# mc34063.net
KiCad netlist of a schematic drawn in EAGLE
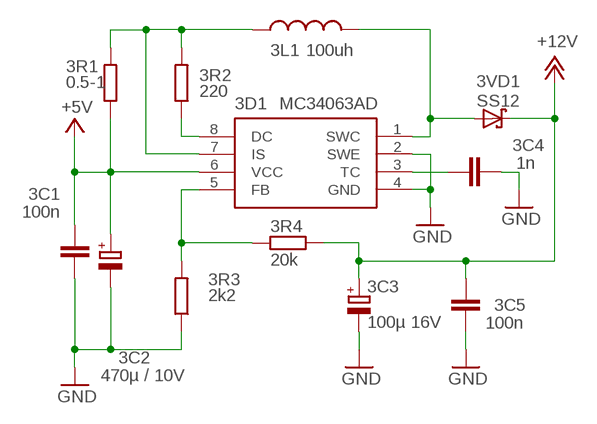
[diagram p0: schematic, sheet 2]

(export (version "E")
  (design (tool "Eeschema 10.0.6"))
  (components
    (comp (ref "3C1")
      (value "100n")
      (footprint "eagle-import:C025-024X044")
      (libsource (lib "eagle-import") (part "C-EU025-024X044"))
    )
    (comp (ref "3C2")
      (value "470µ / 10V")
      (footprint "eagle-import:RCL_E3,5-8")
      (libsource (lib "eagle-import") (part "RCL_CPOL-EUE3.5-8"))
    )
    (comp (ref "3C3")
      (value "100µ 16V")
      (footprint "eagle-import:RCL_E3,5-8")
      (libsource (lib "eagle-import") (part "RCL_CPOL-EUE3.5-8"))
    )
    (comp (ref "3C4")
      (value "1n")
      (footprint "eagle-import:C025-025X050")
      (libsource (lib "eagle-import") (part "rcl_C-EU025-025X050"))
    )
    (comp (ref "3C5")
      (value "100n")
      (footprint "eagle-import:C025-025X050")
      (libsource (lib "eagle-import") (part "rcl_C-EU025-025X050"))
    )
    (comp (ref "3D1")
      (value "MC34063AD")
      (footprint "eagle-import:SOIC8")
      (libsource (lib "eagle-import") (part "MC34063AD"))
    )
    (comp (ref "3L1")
      (value "100uh")
      (footprint "eagle-import:0207_10")
      (libsource (lib "eagle-import") (part "L-US0207/10"))
    )
    (comp (ref "3R1")
      (value "0.5-1")
      (footprint "eagle-import:0204_7")
      (libsource (lib "eagle-import") (part "R-EU_0204/7"))
    )
    (comp (ref "3R2")
      (value "220")
      (footprint "eagle-import:0204_7")
      (libsource (lib "eagle-import") (part "R-EU_0204/7"))
    )
    (comp (ref "3R3")
      (value "2k2")
      (footprint "eagle-import:M0805")
      (libsource (lib "eagle-import") (part "R-EU_M0805"))
    )
    (comp (ref "3R4")
      (value "20k")
      (footprint "eagle-import:M0805")
      (libsource (lib "eagle-import") (part "R-EU_M0805"))
    )
    (comp (ref "3VD1")
      (value "SS12")
      (footprint "eagle-import:SMB")
      (libsource (lib "eagle-import") (part "SCHOTTKY-DIODESMD"))
    )
  )
  (nets
    (net (code "1") (name "+5V") (class "Default")
      (node (ref "3C1") (pin "1") (pinfunction "1_1") (pintype "passive"))
      (node (ref "3C2") (pin "+") (pinfunction "+_+") (pintype "passive"))
      (node (ref "3D1") (pin "6") (pinfunction "VCC_6") (pintype "passive"))
      (node (ref "3R1") (pin "1") (pinfunction "1_1") (pintype "passive"))
    )
    (net (code "2") (name "+12V") (class "Default")
      (node (ref "3C3") (pin "+") (pinfunction "+_+") (pintype "passive"))
      (node (ref "3C5") (pin "2") (pinfunction "2_2") (pintype "passive"))
      (node (ref "3R4") (pin "2") (pinfunction "2_2") (pintype "passive"))
      (node (ref "3VD1") (pin "C") (pinfunction "C_C") (pintype "passive"))
    )
    (net (code "3") (name "GND") (class "Default")
      (node (ref "3C1") (pin "2") (pinfunction "2_2") (pintype "passive"))
      (node (ref "3C2") (pin "-") (pinfunction "-_-") (pintype "passive"))
      (node (ref "3C3") (pin "-") (pinfunction "-_-") (pintype "passive"))
      (node (ref "3C4") (pin "2") (pinfunction "2_2") (pintype "passive"))
      (node (ref "3C5") (pin "1") (pinfunction "1_1") (pintype "passive"))
      (node (ref "3D1") (pin "2") (pinfunction "SWE_2") (pintype "passive"))
      (node (ref "3D1") (pin "4") (pinfunction "GND_4") (pintype "passive"))
      (node (ref "3R3") (pin "1") (pinfunction "1_1") (pintype "passive"))
    )
    (net (code "4") (name "Net-(3D1-DC)") (class "Default")
      (node (ref "3D1") (pin "8") (pinfunction "DC_8") (pintype "passive"))
      (node (ref "3R2") (pin "1") (pinfunction "1_1") (pintype "passive"))
    )
    (net (code "5") (name "Net-(3D1-FB)") (class "Default")
      (node (ref "3D1") (pin "5") (pinfunction "FB_5") (pintype "passive"))
      (node (ref "3R3") (pin "2") (pinfunction "2_2") (pintype "passive"))
      (node (ref "3R4") (pin "1") (pinfunction "1_1") (pintype "passive"))
    )
    (net (code "6") (name "Net-(3D1-IS)") (class "Default")
      (node (ref "3D1") (pin "7") (pinfunction "IS_7") (pintype "passive"))
      (node (ref "3L1") (pin "1") (pinfunction "1_1") (pintype "passive"))
      (node (ref "3R1") (pin "2") (pinfunction "2_2") (pintype "passive"))
      (node (ref "3R2") (pin "2") (pinfunction "2_2") (pintype "passive"))
    )
    (net (code "7") (name "Net-(3D1-SWC)") (class "Default")
      (node (ref "3D1") (pin "1") (pinfunction "SWC_1") (pintype "passive"))
      (node (ref "3L1") (pin "2") (pinfunction "2_2") (pintype "passive"))
      (node (ref "3VD1") (pin "A") (pinfunction "A_A") (pintype "passive"))
    )
    (net (code "8") (name "Net-(3D1-TC)") (class "Default")
      (node (ref "3C4") (pin "1") (pinfunction "1_1") (pintype "passive"))
      (node (ref "3D1") (pin "3") (pinfunction "TC_3") (pintype "passive"))
    )
  )
)
